# opamp_swing.net
KiCad netlist of a schematic drawn in EAGLE
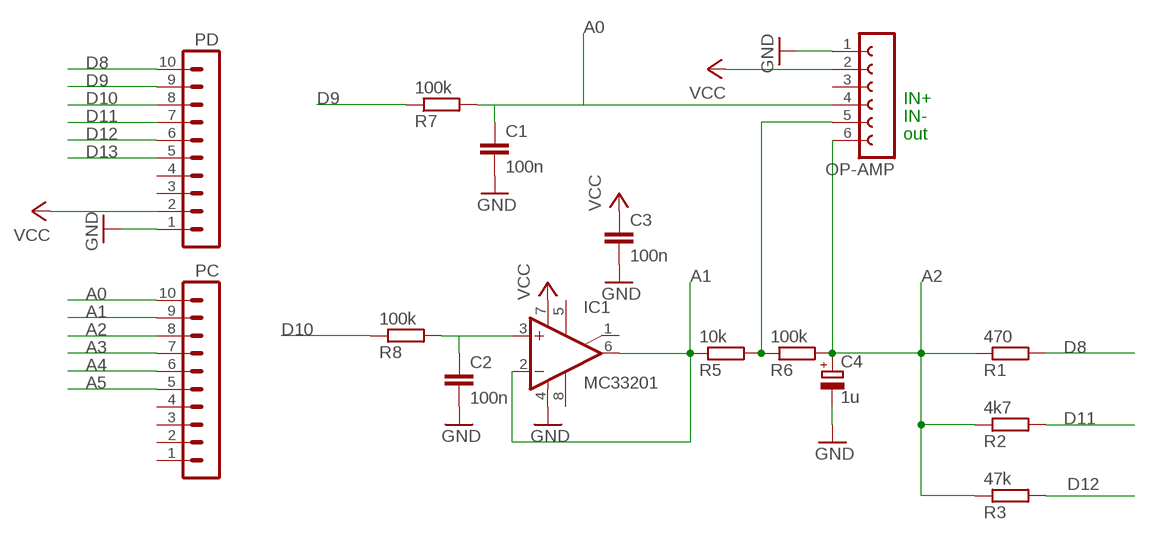
[diagram p0: schematic, sheet 1]

(export (version "E")
  (design (tool "Eeschema 10.0.6"))
  (components
    (comp (ref "C1")
      (value "100n")
      (footprint "eagle-import:C050-025X075")
      (libsource (lib "eagle-import") (part "C-EU050-025X075"))
    )
    (comp (ref "C2")
      (value "100n")
      (footprint "eagle-import:C025-024X044")
      (libsource (lib "eagle-import") (part "C-EU025-024X044"))
    )
    (comp (ref "C3")
      (value "100n")
      (footprint "eagle-import:C025-024X044")
      (libsource (lib "eagle-import") (part "C-EU025-024X044"))
    )
    (comp (ref "C4")
      (value "1u")
      (footprint "eagle-import:153CLV-0405")
      (libsource (lib "eagle-import") (part "CPOL-EU153CLV-0405"))
    )
    (comp (ref "IC1")
      (value "MC33201")
      (footprint "eagle-import:DIL08")
      (libsource (lib "eagle-import") (part "CA3130N"))
    )
    (comp (ref "OP-AMP")
      (value "FE06W")
      (footprint "eagle-import:FE06W")
      (libsource (lib "eagle-import") (part "FE06W"))
    )
    (comp (ref "PC")
      (value "MA10-1W")
      (footprint "eagle-import:MA10-1W")
      (libsource (lib "eagle-import") (part "MA10-1W"))
    )
    (comp (ref "PD")
      (value "MA10-1W")
      (footprint "eagle-import:MA10-1W")
      (libsource (lib "eagle-import") (part "MA10-1W"))
    )
    (comp (ref "R1")
      (value "470")
      (footprint "eagle-import:R1206")
      (libsource (lib "eagle-import") (part "R-EU_R1206"))
    )
    (comp (ref "R2")
      (value "4k7")
      (footprint "eagle-import:R1206")
      (libsource (lib "eagle-import") (part "R-EU_R1206"))
    )
    (comp (ref "R3")
      (value "47k")
      (footprint "eagle-import:R1206")
      (libsource (lib "eagle-import") (part "R-EU_R1206"))
    )
    (comp (ref "R5")
      (value "10k")
      (footprint "eagle-import:0207_12")
      (libsource (lib "eagle-import") (part "R-EU_0207/12"))
    )
    (comp (ref "R6")
      (value "100k")
      (footprint "eagle-import:0207_2V")
      (libsource (lib "eagle-import") (part "R-EU_0207/2V"))
    )
    (comp (ref "R7")
      (value "100k")
      (footprint "eagle-import:0207_15")
      (libsource (lib "eagle-import") (part "R-EU_0207/15"))
    )
    (comp (ref "R8")
      (value "100k")
      (footprint "eagle-import:0207_15")
      (libsource (lib "eagle-import") (part "R-EU_0207/15"))
    )
  )
  (nets
    (net (code "1") (name "/A0") (class "Default")
      (node (ref "C1") (pin "1") (pinfunction "1_1") (pintype "passive"))
      (node (ref "OP-AMP") (pin "4") (pinfunction "4_4") (pintype "passive"))
      (node (ref "PC") (pin "10") (pinfunction "10_10") (pintype "passive"))
      (node (ref "R7") (pin "2") (pinfunction "2_2") (pintype "passive"))
    )
    (net (code "2") (name "/A1") (class "Default")
      (node (ref "IC1") (pin "2") (pinfunction "-IN_2") (pintype "input"))
      (node (ref "IC1") (pin "6") (pinfunction "OUT_6") (pintype "output"))
      (node (ref "PC") (pin "9") (pinfunction "9_9") (pintype "passive"))
      (node (ref "R5") (pin "1") (pinfunction "1_1") (pintype "passive"))
    )
    (net (code "3") (name "/A2") (class "Default")
      (node (ref "C4") (pin "+") (pinfunction "+_+") (pintype "passive"))
      (node (ref "OP-AMP") (pin "6") (pinfunction "6_6") (pintype "passive"))
      (node (ref "PC") (pin "8") (pinfunction "8_8") (pintype "passive"))
      (node (ref "R1") (pin "1") (pinfunction "1_1") (pintype "passive"))
      (node (ref "R2") (pin "1") (pinfunction "1_1") (pintype "passive"))
      (node (ref "R3") (pin "1") (pinfunction "1_1") (pintype "passive"))
      (node (ref "R6") (pin "2") (pinfunction "2_2") (pintype "passive"))
    )
    (net (code "4") (name "/A3") (class "Default")
      (node (ref "PC") (pin "7") (pinfunction "7_7") (pintype "passive"))
    )
    (net (code "5") (name "/A4") (class "Default")
      (node (ref "PC") (pin "6") (pinfunction "6_6") (pintype "passive"))
    )
    (net (code "6") (name "/A5") (class "Default")
      (node (ref "PC") (pin "5") (pinfunction "5_5") (pintype "passive"))
    )
    (net (code "7") (name "/D8") (class "Default")
      (node (ref "PD") (pin "10") (pinfunction "10_10") (pintype "passive"))
      (node (ref "R1") (pin "2") (pinfunction "2_2") (pintype "passive"))
    )
    (net (code "8") (name "/D9") (class "Default")
      (node (ref "PD") (pin "9") (pinfunction "9_9") (pintype "passive"))
      (node (ref "R7") (pin "1") (pinfunction "1_1") (pintype "passive"))
    )
    (net (code "9") (name "/D10") (class "Default")
      (node (ref "PD") (pin "8") (pinfunction "8_8") (pintype "passive"))
      (node (ref "R8") (pin "1") (pinfunction "1_1") (pintype "passive"))
    )
    (net (code "10") (name "/D11") (class "Default")
      (node (ref "PD") (pin "7") (pinfunction "7_7") (pintype "passive"))
      (node (ref "R2") (pin "2") (pinfunction "2_2") (pintype "passive"))
    )
    (net (code "11") (name "/D12") (class "Default")
      (node (ref "PD") (pin "6") (pinfunction "6_6") (pintype "passive"))
      (node (ref "R3") (pin "2") (pinfunction "2_2") (pintype "passive"))
    )
    (net (code "12") (name "/D13") (class "Default")
      (node (ref "PD") (pin "5") (pinfunction "5_5") (pintype "passive"))
    )
    (net (code "13") (name "GND") (class "Default")
      (node (ref "C1") (pin "2") (pinfunction "2_2") (pintype "passive"))
      (node (ref "C2") (pin "2") (pinfunction "2_2") (pintype "passive"))
      (node (ref "C3") (pin "2") (pinfunction "2_2") (pintype "passive"))
      (node (ref "C4") (pin "-") (pinfunction "-_-") (pintype "passive"))
      (node (ref "IC1") (pin "4") (pinfunction "V-_4") (pintype "power_in"))
      (node (ref "OP-AMP") (pin "1") (pinfunction "1_1") (pintype "passive"))
      (node (ref "PD") (pin "1") (pinfunction "1_1") (pintype "passive"))
    )
    (net (code "14") (name "Net-(IC1-+IN)") (class "Default")
      (node (ref "C2") (pin "1") (pinfunction "1_1") (pintype "passive"))
      (node (ref "IC1") (pin "3") (pinfunction "+IN_3") (pintype "input"))
      (node (ref "R8") (pin "2") (pinfunction "2_2") (pintype "passive"))
    )
    (net (code "15") (name "Net-(OP-AMP-Pad5)") (class "Default")
      (node (ref "OP-AMP") (pin "5") (pinfunction "5_5") (pintype "passive"))
      (node (ref "R5") (pin "2") (pinfunction "2_2") (pintype "passive"))
      (node (ref "R6") (pin "1") (pinfunction "1_1") (pintype "passive"))
    )
    (net (code "16") (name "VCC") (class "Default")
      (node (ref "C3") (pin "1") (pinfunction "1_1") (pintype "passive"))
      (node (ref "IC1") (pin "7") (pinfunction "V+_7") (pintype "power_in"))
      (node (ref "OP-AMP") (pin "2") (pinfunction "2_2") (pintype "passive"))
      (node (ref "PD") (pin "2") (pinfunction "2_2") (pintype "passive"))
    )
    (net (code "17") (name "unconnected-(IC1-CMP-Pad8)") (class "Default")
      (node (ref "IC1") (pin "8") (pinfunction "CMP_8") (pintype "passive"))
    )
    (net (code "18") (name "unconnected-(IC1-ON-Pad5)") (class "Default")
      (node (ref "IC1") (pin "5") (pinfunction "ON_5") (pintype "passive"))
    )
    (net (code "19") (name "unconnected-(IC1-ON{slash}CMP-Pad1)") (class "Default")
      (node (ref "IC1") (pin "1") (pinfunction "ON/CMP_1") (pintype "passive"))
    )
    (net (code "20") (name "unconnected-(OP-AMP-Pad3)") (class "Default")
      (node (ref "OP-AMP") (pin "3") (pinfunction "3_3") (pintype "passive"))
    )
    (net (code "21") (name "unconnected-(PC-Pad1)") (class "Default")
      (node (ref "PC") (pin "1") (pinfunction "1_1") (pintype "passive"))
    )
    (net (code "22") (name "unconnected-(PC-Pad2)") (class "Default")
      (node (ref "PC") (pin "2") (pinfunction "2_2") (pintype "passive"))
    )
    (net (code "23") (name "unconnected-(PC-Pad3)") (class "Default")
      (node (ref "PC") (pin "3") (pinfunction "3_3") (pintype "passive"))
    )
    (net (code "24") (name "unconnected-(PC-Pad4)") (class "Default")
      (node (ref "PC") (pin "4") (pinfunction "4_4") (pintype "passive"))
    )
    (net (code "25") (name "unconnected-(PD-Pad3)") (class "Default")
      (node (ref "PD") (pin "3") (pinfunction "3_3") (pintype "passive"))
    )
    (net (code "26") (name "unconnected-(PD-Pad4)") (class "Default")
      (node (ref "PD") (pin "4") (pinfunction "4_4") (pintype "passive"))
    )
  )
)
